# NFC_SCH.net
KiCad netlist of a schematic drawn in Altium Designer
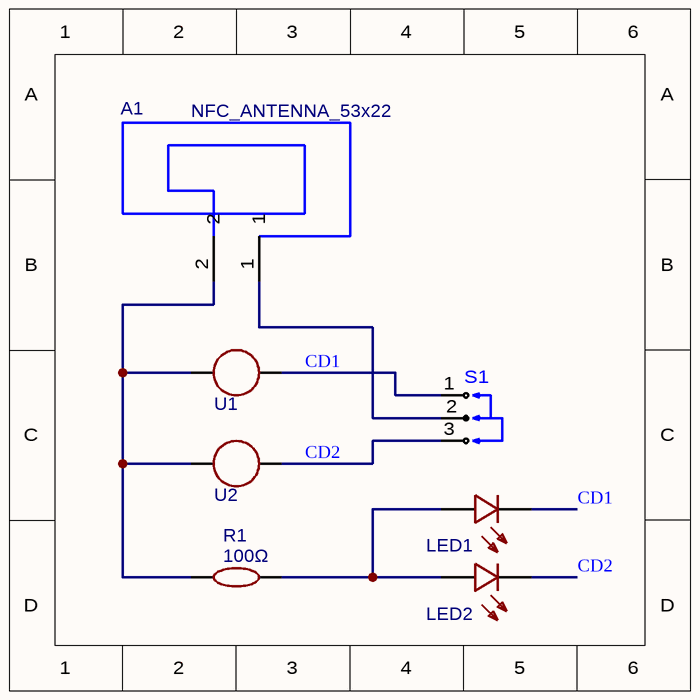
[diagram p0: NFC_SCH.schdoc]

(export (version "E")
  (design (tool "Eeschema 10.0.6"))
  (components
    (comp (ref "A1")
      (value "NFC_ANTENNA_53x22")
      (footprint "NFC_ANTENNA_53X22")
      (fields (field (name "CONTRIBUTOR") "Lockon"))
      (libsource (lib "NFC_SCHLIB") (part "NFC_ANTENNA_53x22"))
    )
    (comp (ref "LED1")
      (value "BL-HB337A-AV-TRB")
      (footprint "LED 0805R")
      (fields (field (name "BOM_SUPPLIER PART") "C165977") (field (name "CONTRIBUTOR") "LCSC"))
      (libsource (lib "altium-import") (part "root_2_BL-HB337A-AV-TRB_"))
    )
    (comp (ref "LED2")
      (value "BL-HB337A-AV-TRB")
      (footprint "LED 0805R")
      (fields (field (name "BOM_SUPPLIER PART") "C165977") (field (name "CONTRIBUTOR") "LCSC"))
      (libsource (lib "altium-import") (part "root_2_BL-HB337A-AV-TRB_"))
    )
    (comp (ref "R1")
      (value "100Ω")
      (footprint "R 0805_L")
      (fields
        (field (name "BOM_MANUFACTURER PART") "0402WGF1000TCE")
        (field (name "BOM_SUPPLIER PART") "C25076")
      )
      (libsource (lib "altium-import") (part "root_0_100Ω_"))
    )
    (comp (ref "S1") (value "~") (footprint "KEY") (libsource (lib "NFC_SCHLIB") (part "SS12D10G4 071")))
    (comp (ref "U1")
      (value "NFC Chip")
      (footprint "COB-213")
      (fields
        (field (name "BOM_MANUFACTURER PART") "0603WAF1002T5E")
        (field (name "BOM_SUPPLIER PART") "C25804")
      )
      (libsource (lib "NFC_SCHLIB") (part "NFC Chip"))
    )
    (comp (ref "U2")
      (value "NFC Chip")
      (footprint "COB-213")
      (fields
        (field (name "BOM_MANUFACTURER PART") "0603WAF1002T5E")
        (field (name "BOM_SUPPLIER PART") "C25804")
      )
      (libsource (lib "NFC_SCHLIB") (part "NFC Chip"))
    )
  )
  (nets
    (net (code "1") (name "/CD1") (class "Default")
      (node (ref "LED1") (pin "1") (pinfunction "K_1") (pintype "passive"))
      (node (ref "S1") (pin "1") (pinfunction "1_1") (pintype "passive"))
      (node (ref "U1") (pin "2") (pinfunction "2_2") (pintype "passive"))
    )
    (net (code "2") (name "/CD2") (class "Default")
      (node (ref "LED2") (pin "1") (pinfunction "K_1") (pintype "passive"))
      (node (ref "S1") (pin "3") (pinfunction "3_3") (pintype "passive"))
      (node (ref "U2") (pin "2") (pinfunction "2_2") (pintype "passive"))
    )
    (net (code "3") (name "Net-(A1-Pad1)") (class "Default")
      (node (ref "A1") (pin "1") (pinfunction "1_1") (pintype "passive"))
      (node (ref "S1") (pin "2") (pinfunction "2_2") (pintype "passive"))
    )
    (net (code "4") (name "Net-(A1-Pad2)") (class "Default")
      (node (ref "A1") (pin "2") (pinfunction "2_2") (pintype "passive"))
      (node (ref "R1") (pin "1") (pinfunction "1_1") (pintype "passive"))
      (node (ref "U1") (pin "1") (pinfunction "1_1") (pintype "passive"))
      (node (ref "U2") (pin "1") (pinfunction "1_1") (pintype "passive"))
    )
    (net (code "5") (name "Net-(LED1-A)") (class "Default")
      (node (ref "LED1") (pin "2") (pinfunction "A_2") (pintype "passive"))
      (node (ref "LED2") (pin "2") (pinfunction "A_2") (pintype "passive"))
      (node (ref "R1") (pin "2") (pinfunction "2_2") (pintype "passive"))
    )
  )
)
